# SAMV71_Xplained_Ultra_CAN.net
KiCad netlist of a schematic drawn in Altium Designer
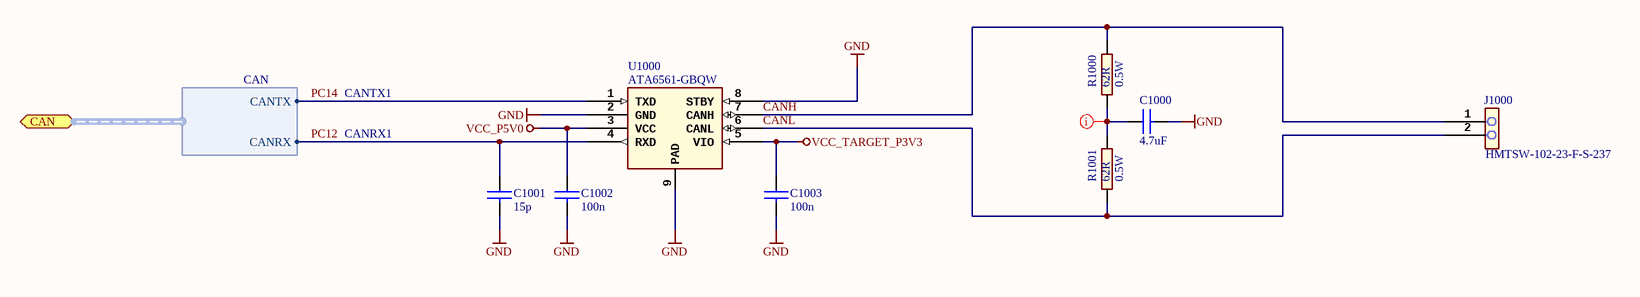
[diagram p0: SAMV71_Xplained_Ultra_CAN.SchDoc]

(export (version "E")
  (design (tool "Eeschema 10.0.6"))
  (components
    (comp (ref "C1000")
      (value "4.7uF")
      (footprint "AP1-00003")
      (description "Ceramic capacitor, SMD 0805, X5R, 25V, ±10 %")
      (fields (field (name "TOLERANCE") "±10%") (field (name "MANUFACTURER") "Murata"))
      (libsource (lib "AltiumDbLib") (part "CAP-NONPOL"))
    )
    (comp (ref "C1001")
      (value "15p")
      (footprint "AP1-00001")
      (description "Ceramic capacitor, SMD 0402, NP0, 50V, +/-5%")
      (fields (field (name "TOLERANCE") "50V, +/-5%") (field (name "Comment") "CAP-NONPOL"))
      (libsource (lib "AltiumDbLib") (part "CAP-NONPOL"))
    )
    (comp (ref "C1002")
      (value "100n")
      (footprint "AP1-00001")
      (description "Ceramic capacitor, SMD 0402, X7R, 16V, +/-10%")
      (fields (field (name "TOLERANCE") "16V, +/-10%") (field (name "MANUFACTURER") "Kemet"))
      (libsource (lib "AltiumDbLib") (part "CAP-NONPOL"))
    )
    (comp (ref "C1003")
      (value "100n")
      (footprint "AP1-00001")
      (description "Ceramic capacitor, SMD 0402, X7R, 16V, +/-10%")
      (fields (field (name "TOLERANCE") "16V, +/-10%") (field (name "MANUFACTURER") "Kemet"))
      (libsource (lib "AltiumDbLib") (part "CAP-NONPOL"))
    )
    (comp (ref "J1000")
      (value "HMTSW-102-23-F-S-237")
      (footprint "AP8-00733")
      (description "1x2 pin header, 2.54mm pitch, Pin-in-Paste THM")
      (fields (field (name "MANUFACTURER") "SAMTEC") (field (name "Comment") "HEADER 1x2"))
      (libsource (lib "AltiumDbLib") (part "HEADER 1x2"))
    )
    (comp (ref "R1000")
      (value "0.5W")
      (footprint "AP2-00008")
      (description "Thick film resistor, SMD 1210, 0.5W, 1%")
      (fields (field (name "ALTIUM_VALUE") "62R") (field (name "TOLERANCE") "1%"))
      (libsource (lib "AltiumDbLib") (part "R2"))
    )
    (comp (ref "R1001")
      (value "0.5W")
      (footprint "AP2-00008")
      (description "Thick film resistor, SMD 1210, 0.5W, 1%")
      (fields (field (name "ALTIUM_VALUE") "62R") (field (name "TOLERANCE") "1%"))
      (libsource (lib "AltiumDbLib") (part "R2"))
    )
    (comp (ref "U1000")
      (value "ATA6561-GBQW")
      (footprint "AP6-00407")
      (description "5Mbit/s CAN Trasceiver,VCC = 5V, VIO = 2.8-5V, 3x3 mm VDFN8")
      (fields (field (name "Comment") "ATA6561"))
      (libsource (lib "AltiumDbLib") (part "ATA6561"))
    )
  )
  (nets
    (net (code "2") (name "/CANH") (class "Default")
      (node (ref "J1000") (pin "1") (pinfunction "1_1") (pintype "passive"))
      (node (ref "R1000") (pin "2") (pinfunction "2_2") (pintype "passive"))
      (node (ref "U1000") (pin "7") (pinfunction "CANH_7") (pintype "bidirectional"))
    )
    (net (code "3") (name "/CANL") (class "Default")
      (node (ref "J1000") (pin "2") (pinfunction "2_2") (pintype "passive"))
      (node (ref "R1001") (pin "1") (pinfunction "1_1") (pintype "passive"))
      (node (ref "U1000") (pin "6") (pinfunction "CANL_6") (pintype "bidirectional"))
    )
    (net (code "4") (name "/PC12") (class "Default")
      (node (ref "C1001") (pin "1") (pinfunction "1_1") (pintype "passive"))
      (node (ref "U1000") (pin "4") (pinfunction "RXD_4") (pintype "output"))
    )
    (net (code "5") (name "/PC14") (class "Default")
      (node (ref "U1000") (pin "1") (pinfunction "TXD_1") (pintype "input"))
    )
    (net (code "7") (name "GND") (class "Default")
      (node (ref "C1000") (pin "2") (pinfunction "2_2") (pintype "passive"))
      (node (ref "C1001") (pin "2") (pinfunction "2_2") (pintype "passive"))
      (node (ref "C1002") (pin "2") (pinfunction "2_2") (pintype "passive"))
      (node (ref "C1003") (pin "2") (pinfunction "2_2") (pintype "passive"))
      (node (ref "U1000") (pin "2") (pinfunction "GND_2") (pintype "power_in"))
      (node (ref "U1000") (pin "8") (pinfunction "STBY_8") (pintype "input"))
      (node (ref "U1000") (pin "9") (pinfunction "PAD_9") (pintype "power_in"))
    )
    (net (code "8") (name "Net-(C1000-Pad1)") (class "Default")
      (node (ref "C1000") (pin "1") (pinfunction "1_1") (pintype "passive"))
      (node (ref "R1000") (pin "1") (pinfunction "1_1") (pintype "passive"))
      (node (ref "R1001") (pin "2") (pinfunction "2_2") (pintype "passive"))
    )
    (net (code "9") (name "VCC_P5V0") (class "Default")
      (node (ref "C1002") (pin "1") (pinfunction "1_1") (pintype "passive"))
      (node (ref "U1000") (pin "3") (pinfunction "VCC_3") (pintype "power_in"))
    )
    (net (code "10") (name "VCC_TARGET_P3V3") (class "Default")
      (node (ref "C1003") (pin "1") (pinfunction "1_1") (pintype "passive"))
      (node (ref "U1000") (pin "5") (pinfunction "VIO_5") (pintype "input"))
    )
  )
)
